# S7CAS-PLEIADES-CARTE-MERE_P06_FPGA4.net
KiCad netlist of a schematic drawn in Altium Designer
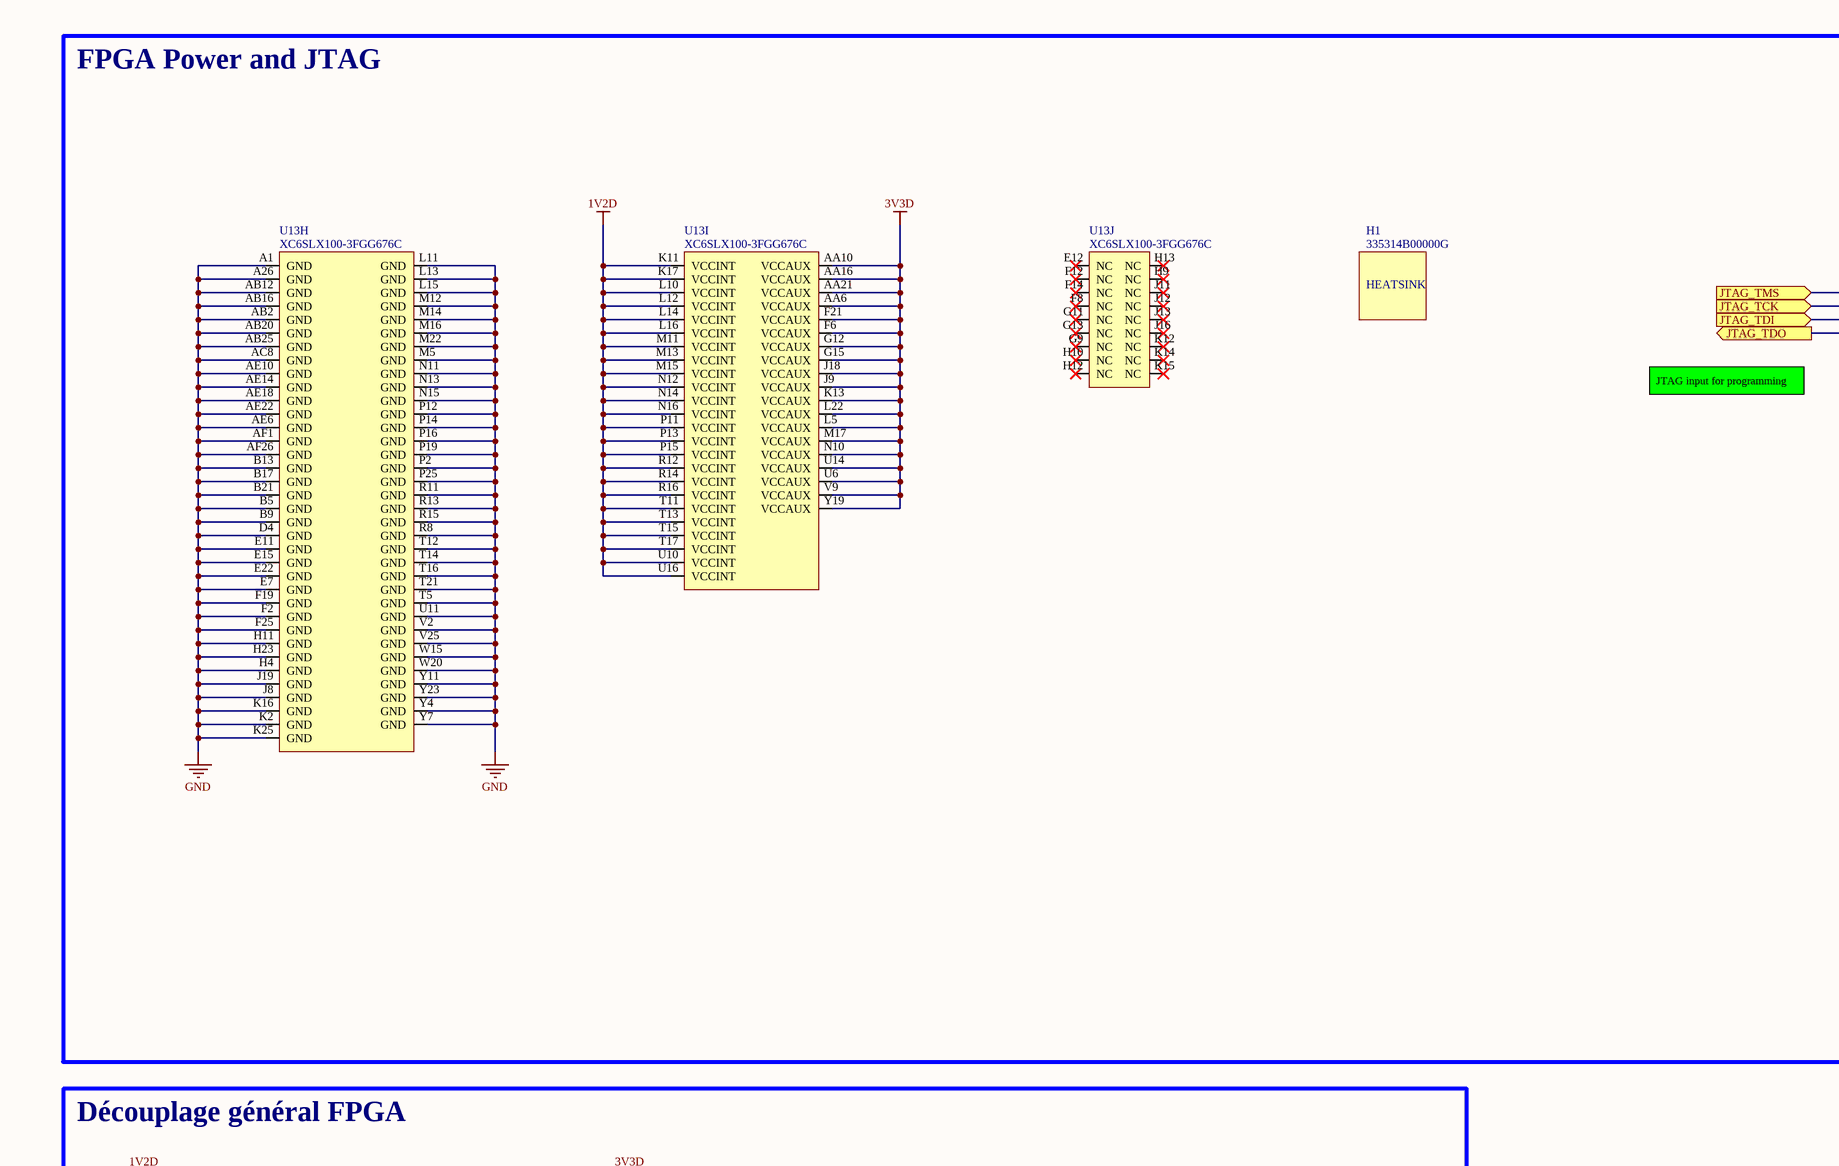
[diagram p0: S7CAS-PLEIADES-CARTE-MERE_P06_FPGA4.SCHDOC, top left]
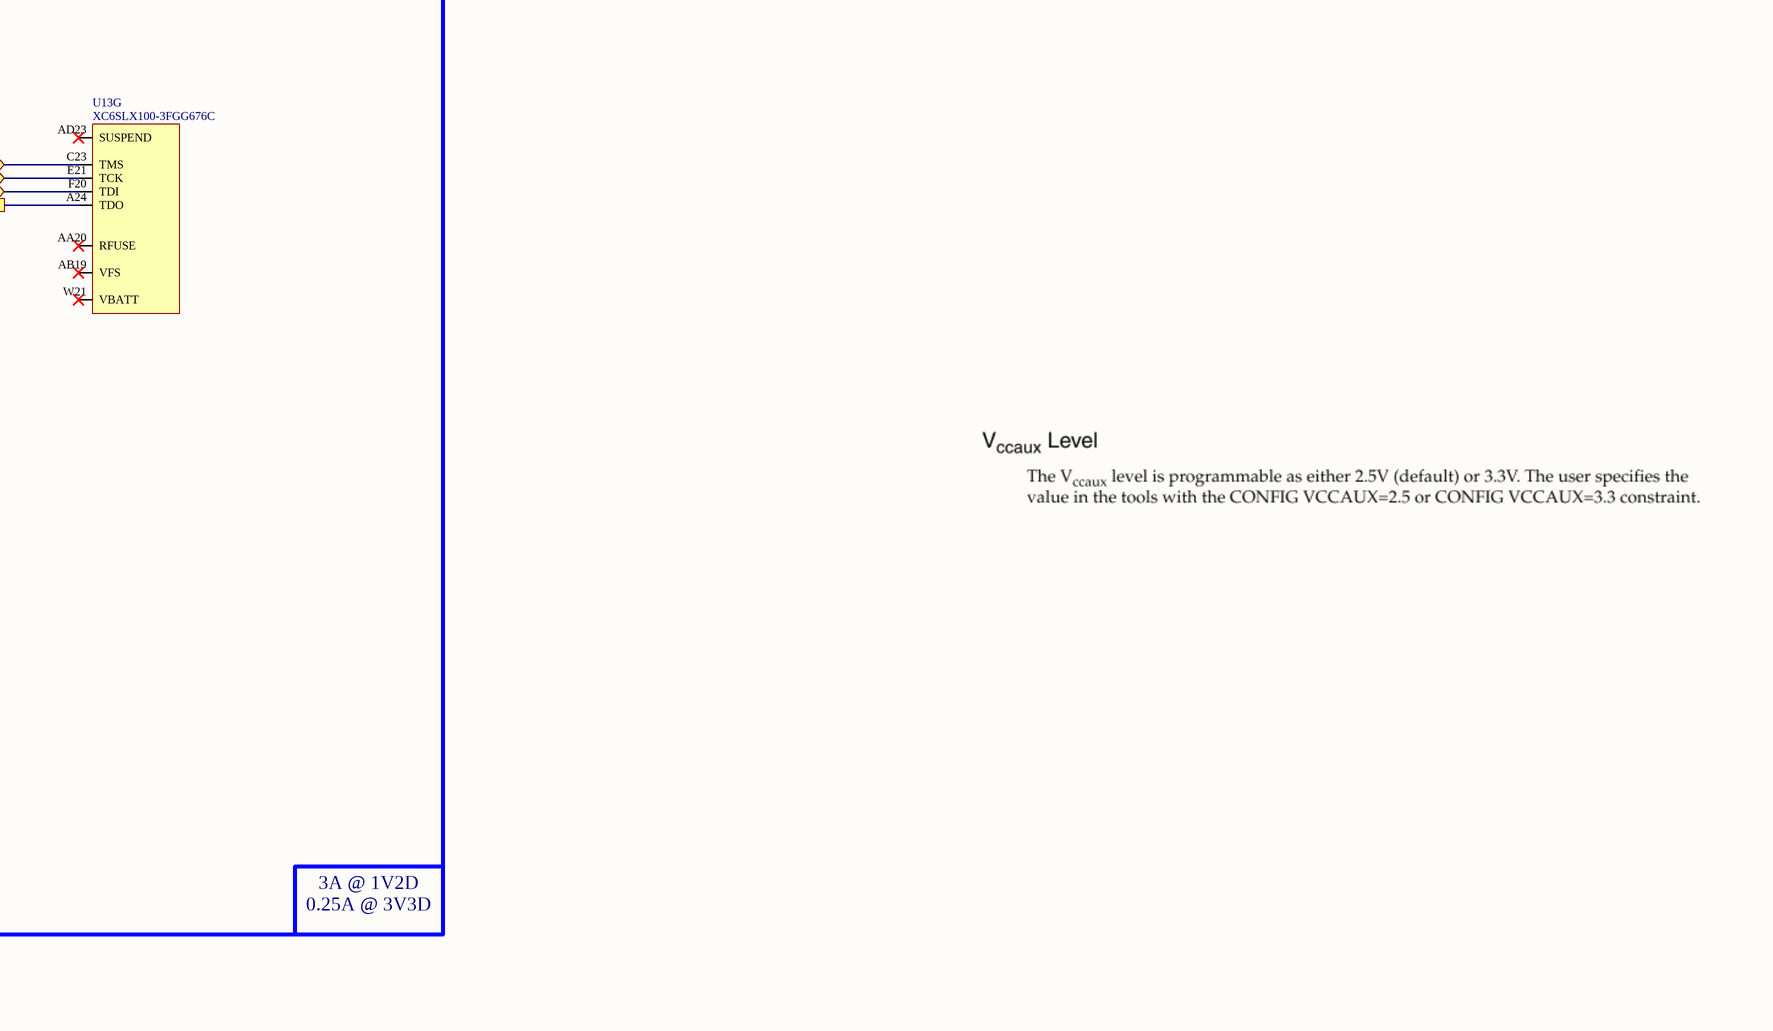
[diagram p1: S7CAS-PLEIADES-CARTE-MERE_P06_FPGA4.SCHDOC, top right]
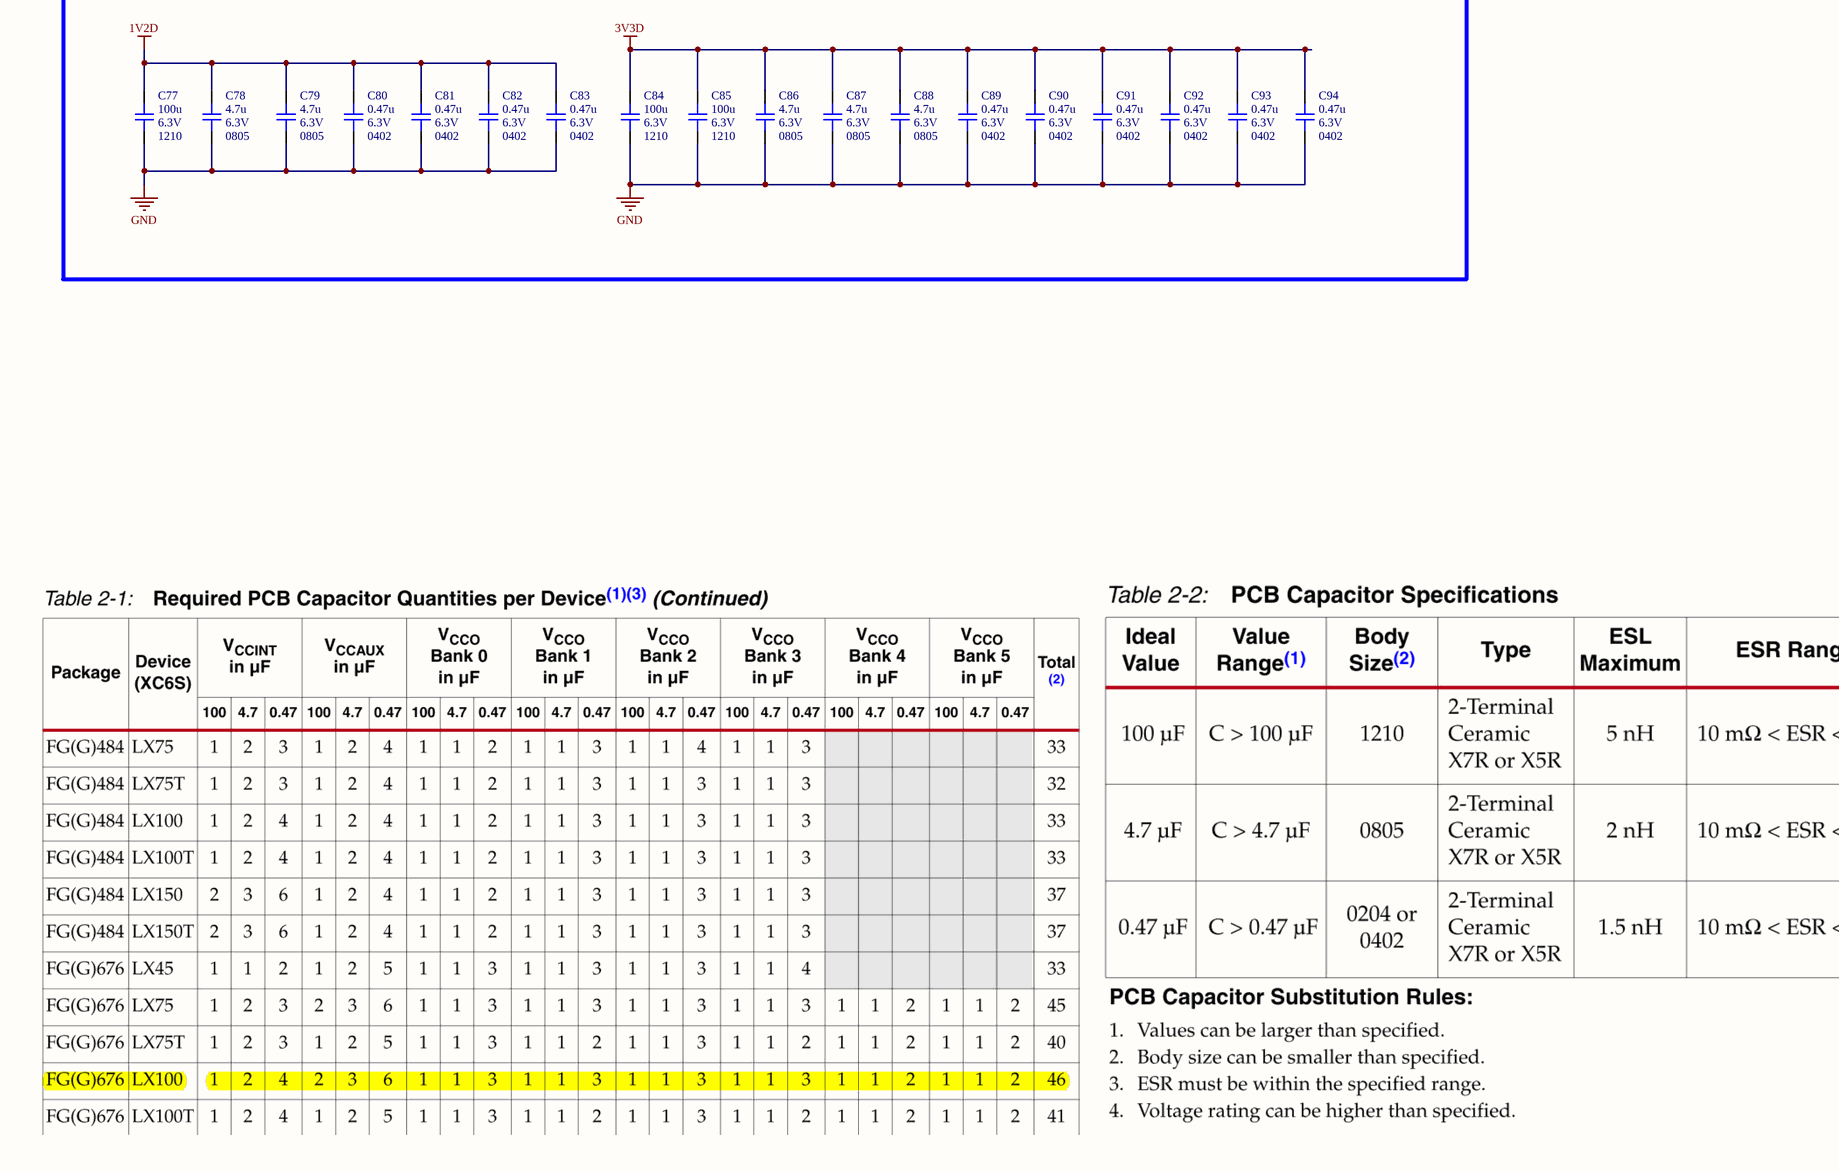
[diagram p2: S7CAS-PLEIADES-CARTE-MERE_P06_FPGA4.SCHDOC, bottom left]
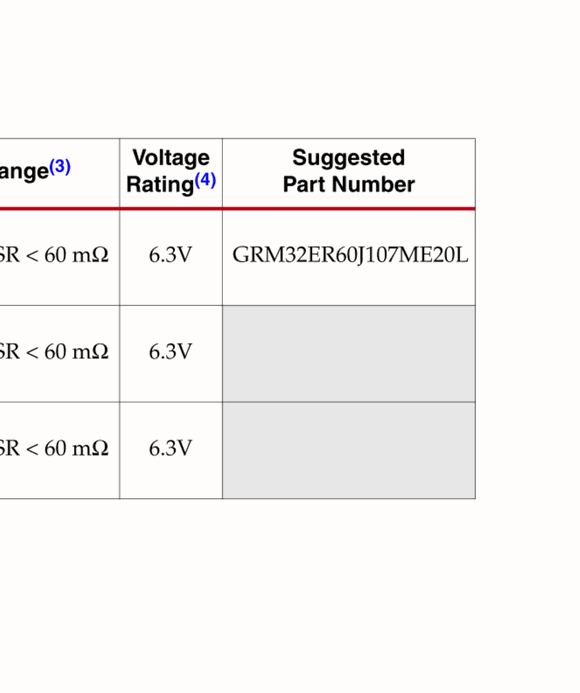
[diagram p3: S7CAS-PLEIADES-CARTE-MERE_P06_FPGA4.SCHDOC, bottom right]

(export (version "E")
  (design (tool "Eeschema 10.0.6"))
  (components
    (comp (ref "C77")
      (value "100u")
      (footprint "CAP_1210")
      (description "CAP - 1210")
      (fields
        (field (name "VOLTAGE") "6.3V")
        (field (name "PACKAGE") "1210")
        (field (name "CREATEDBY") "Jonathan Bouchard")
      )
      (libsource (lib "s7cas_lib2023") (part "CAP - 1210"))
    )
    (comp (ref "C78")
      (value "4.7u")
      (footprint "CAP_0805")
      (description "CAP - 0805")
      (fields
        (field (name "VOLTAGE") "6.3V")
        (field (name "PACKAGE") "0805")
        (field (name "CREATEDBY") "Jonathan Bouchard")
      )
      (libsource (lib "s7cas_lib2023") (part "CAP - 0805"))
    )
    (comp (ref "C79")
      (value "4.7u")
      (footprint "CAP_0805")
      (description "CAP - 0805")
      (fields
        (field (name "VOLTAGE") "6.3V")
        (field (name "PACKAGE") "0805")
        (field (name "CREATEDBY") "Jonathan Bouchard")
      )
      (libsource (lib "s7cas_lib2023") (part "CAP - 0805"))
    )
    (comp (ref "C80")
      (value "0.47u")
      (footprint "CAP_0402")
      (description "CAP - 0402")
      (fields
        (field (name "VOLTAGE") "6.3V")
        (field (name "PACKAGE") "0402")
        (field (name "CREATEDBY") "Jonathan Bouchard")
      )
      (libsource (lib "s7cas_lib2023") (part "CAP - 0402"))
    )
    (comp (ref "C81")
      (value "0.47u")
      (footprint "CAP_0402")
      (description "CAP - 0402")
      (fields
        (field (name "VOLTAGE") "6.3V")
        (field (name "PACKAGE") "0402")
        (field (name "CREATEDBY") "Jonathan Bouchard")
      )
      (libsource (lib "s7cas_lib2023") (part "CAP - 0402"))
    )
    (comp (ref "C82")
      (value "0.47u")
      (footprint "CAP_0402")
      (description "CAP - 0402")
      (fields
        (field (name "VOLTAGE") "6.3V")
        (field (name "PACKAGE") "0402")
        (field (name "CREATEDBY") "Jonathan Bouchard")
      )
      (libsource (lib "s7cas_lib2023") (part "CAP - 0402"))
    )
    (comp (ref "C83")
      (value "0.47u")
      (footprint "CAP_0402")
      (description "CAP - 0402")
      (fields
        (field (name "VOLTAGE") "6.3V")
        (field (name "PACKAGE") "0402")
        (field (name "CREATEDBY") "Jonathan Bouchard")
      )
      (libsource (lib "s7cas_lib2023") (part "CAP - 0402"))
    )
    (comp (ref "C84")
      (value "100u")
      (footprint "CAP_1210")
      (description "CAP - 1210")
      (fields
        (field (name "VOLTAGE") "6.3V")
        (field (name "PACKAGE") "1210")
        (field (name "CREATEDBY") "Jonathan Bouchard")
      )
      (libsource (lib "s7cas_lib2023") (part "CAP - 1210"))
    )
    (comp (ref "C85")
      (value "100u")
      (footprint "CAP_1210")
      (description "CAP - 1210")
      (fields
        (field (name "VOLTAGE") "6.3V")
        (field (name "PACKAGE") "1210")
        (field (name "CREATEDBY") "Jonathan Bouchard")
      )
      (libsource (lib "s7cas_lib2023") (part "CAP - 1210"))
    )
    (comp (ref "C86")
      (value "4.7u")
      (footprint "CAP_0805")
      (description "CAP - 0805")
      (fields
        (field (name "VOLTAGE") "6.3V")
        (field (name "PACKAGE") "0805")
        (field (name "CREATEDBY") "Jonathan Bouchard")
      )
      (libsource (lib "s7cas_lib2023") (part "CAP - 0805"))
    )
    (comp (ref "C87")
      (value "4.7u")
      (footprint "CAP_0805")
      (description "CAP - 0805")
      (fields
        (field (name "VOLTAGE") "6.3V")
        (field (name "PACKAGE") "0805")
        (field (name "CREATEDBY") "Jonathan Bouchard")
      )
      (libsource (lib "s7cas_lib2023") (part "CAP - 0805"))
    )
    (comp (ref "C88")
      (value "4.7u")
      (footprint "CAP_0805")
      (description "CAP - 0805")
      (fields
        (field (name "VOLTAGE") "6.3V")
        (field (name "PACKAGE") "0805")
        (field (name "CREATEDBY") "Jonathan Bouchard")
      )
      (libsource (lib "s7cas_lib2023") (part "CAP - 0805"))
    )
    (comp (ref "C89")
      (value "0.47u")
      (footprint "CAP_0402")
      (description "CAP - 0402")
      (fields
        (field (name "VOLTAGE") "6.3V")
        (field (name "PACKAGE") "0402")
        (field (name "CREATEDBY") "Jonathan Bouchard")
      )
      (libsource (lib "s7cas_lib2023") (part "CAP - 0402"))
    )
    (comp (ref "C90")
      (value "0.47u")
      (footprint "CAP_0402")
      (description "CAP - 0402")
      (fields
        (field (name "VOLTAGE") "6.3V")
        (field (name "PACKAGE") "0402")
        (field (name "CREATEDBY") "Jonathan Bouchard")
      )
      (libsource (lib "s7cas_lib2023") (part "CAP - 0402"))
    )
    (comp (ref "C91")
      (value "0.47u")
      (footprint "CAP_0402")
      (description "CAP - 0402")
      (fields
        (field (name "VOLTAGE") "6.3V")
        (field (name "PACKAGE") "0402")
        (field (name "CREATEDBY") "Jonathan Bouchard")
      )
      (libsource (lib "s7cas_lib2023") (part "CAP - 0402"))
    )
    (comp (ref "C92")
      (value "0.47u")
      (footprint "CAP_0402")
      (description "CAP - 0402")
      (fields
        (field (name "VOLTAGE") "6.3V")
        (field (name "PACKAGE") "0402")
        (field (name "CREATEDBY") "Jonathan Bouchard")
      )
      (libsource (lib "s7cas_lib2023") (part "CAP - 0402"))
    )
    (comp (ref "C93")
      (value "0.47u")
      (footprint "CAP_0402")
      (description "CAP - 0402")
      (fields
        (field (name "VOLTAGE") "6.3V")
        (field (name "PACKAGE") "0402")
        (field (name "CREATEDBY") "Jonathan Bouchard")
      )
      (libsource (lib "s7cas_lib2023") (part "CAP - 0402"))
    )
    (comp (ref "C94")
      (value "0.47u")
      (footprint "CAP_0402")
      (description "CAP - 0402")
      (fields
        (field (name "VOLTAGE") "6.3V")
        (field (name "PACKAGE") "0402")
        (field (name "CREATEDBY") "Jonathan Bouchard")
      )
      (libsource (lib "s7cas_lib2023") (part "CAP - 0402"))
    )
    (comp (ref "H1")
      (value "335314B00000G")
      (description "HSK - Heat sink 335314B00000G 27x27mm")
      (libsource (lib "BGAH270-175E") (part "HSK_335314B00000G"))
    )
    (comp (ref "U13")
      (value "XC6SLX100-3FGG676C")
      (footprint "FPGA_XILINX_FGG676")
      (description "FPGA - XILINX SPARTAN 6 480 I/O - BGA-676")
      (fields
        (field (name "VOLTAGE") "1.14 V ~ 1.26 V")
        (field (name "MFG") "Xilinx")
        (field (name "CREATEDBY") "Jonathan Bouchard")
      )
      (libsource (lib "s7cas_lib2023") (part "FPGA_XC6SLX100-3FGG676C"))
    )
  )
  (nets
    (net (code "1") (name "/JTAG_TCK") (class "Default")
      (node (ref "U13") (pin "E21") (pinfunction "TCK_E21") (pintype "passive"))
    )
    (net (code "2") (name "/JTAG_TDI") (class "Default")
      (node (ref "U13") (pin "F20") (pinfunction "TDI_F20") (pintype "passive"))
    )
    (net (code "3") (name "/JTAG_TDO") (class "Default")
      (node (ref "U13") (pin "A24") (pinfunction "TDO_A24") (pintype "passive"))
    )
    (net (code "4") (name "/JTAG_TMS") (class "Default")
      (node (ref "U13") (pin "C23") (pinfunction "TMS_C23") (pintype "passive"))
    )
    (net (code "5") (name "1V2D") (class "Default")
      (node (ref "C77") (pin "2") (pinfunction "2_2") (pintype "passive"))
      (node (ref "C78") (pin "2") (pinfunction "2_2") (pintype "passive"))
      (node (ref "C79") (pin "2") (pinfunction "2_2") (pintype "passive"))
      (node (ref "C80") (pin "2") (pinfunction "2_2") (pintype "passive"))
      (node (ref "C81") (pin "2") (pinfunction "2_2") (pintype "passive"))
      (node (ref "C82") (pin "2") (pinfunction "2_2") (pintype "passive"))
      (node (ref "C83") (pin "2") (pinfunction "2_2") (pintype "passive"))
      (node (ref "U13") (pin "K11") (pinfunction "VCCINT_K11") (pintype "passive"))
      (node (ref "U13") (pin "K17") (pinfunction "VCCINT_K17") (pintype "passive"))
      (node (ref "U13") (pin "L10") (pinfunction "VCCINT_L10") (pintype "passive"))
      (node (ref "U13") (pin "L12") (pinfunction "VCCINT_L12") (pintype "passive"))
      (node (ref "U13") (pin "L14") (pinfunction "VCCINT_L14") (pintype "passive"))
      (node (ref "U13") (pin "L16") (pinfunction "VCCINT_L16") (pintype "passive"))
      (node (ref "U13") (pin "M11") (pinfunction "VCCINT_M11") (pintype "passive"))
      (node (ref "U13") (pin "M13") (pinfunction "VCCINT_M13") (pintype "passive"))
      (node (ref "U13") (pin "M15") (pinfunction "VCCINT_M15") (pintype "passive"))
      (node (ref "U13") (pin "N12") (pinfunction "VCCINT_N12") (pintype "passive"))
      (node (ref "U13") (pin "N14") (pinfunction "VCCINT_N14") (pintype "passive"))
      (node (ref "U13") (pin "N16") (pinfunction "VCCINT_N16") (pintype "passive"))
      (node (ref "U13") (pin "P11") (pinfunction "VCCINT_P11") (pintype "passive"))
      (node (ref "U13") (pin "P13") (pinfunction "VCCINT_P13") (pintype "passive"))
      (node (ref "U13") (pin "P15") (pinfunction "VCCINT_P15") (pintype "passive"))
      (node (ref "U13") (pin "R12") (pinfunction "VCCINT_R12") (pintype "passive"))
      (node (ref "U13") (pin "R14") (pinfunction "VCCINT_R14") (pintype "passive"))
      (node (ref "U13") (pin "R16") (pinfunction "VCCINT_R16") (pintype "passive"))
      (node (ref "U13") (pin "T11") (pinfunction "VCCINT_T11") (pintype "passive"))
      (node (ref "U13") (pin "T13") (pinfunction "VCCINT_T13") (pintype "passive"))
      (node (ref "U13") (pin "T15") (pinfunction "VCCINT_T15") (pintype "passive"))
      (node (ref "U13") (pin "T17") (pinfunction "VCCINT_T17") (pintype "passive"))
      (node (ref "U13") (pin "U10") (pinfunction "VCCINT_U10") (pintype "passive"))
      (node (ref "U13") (pin "U16") (pinfunction "VCCINT_U16") (pintype "passive"))
    )
    (net (code "6") (name "3V3D") (class "Default")
      (node (ref "C84") (pin "2") (pinfunction "2_2") (pintype "passive"))
      (node (ref "C85") (pin "2") (pinfunction "2_2") (pintype "passive"))
      (node (ref "C86") (pin "2") (pinfunction "2_2") (pintype "passive"))
      (node (ref "C87") (pin "2") (pinfunction "2_2") (pintype "passive"))
      (node (ref "C88") (pin "2") (pinfunction "2_2") (pintype "passive"))
      (node (ref "C89") (pin "2") (pinfunction "2_2") (pintype "passive"))
      (node (ref "C90") (pin "2") (pinfunction "2_2") (pintype "passive"))
      (node (ref "C91") (pin "2") (pinfunction "2_2") (pintype "passive"))
      (node (ref "C92") (pin "2") (pinfunction "2_2") (pintype "passive"))
      (node (ref "C93") (pin "2") (pinfunction "2_2") (pintype "passive"))
      (node (ref "C94") (pin "2") (pinfunction "2_2") (pintype "passive"))
      (node (ref "U13") (pin "AA10") (pinfunction "VCCAUX_AA10") (pintype "passive"))
      (node (ref "U13") (pin "AA16") (pinfunction "VCCAUX_AA16") (pintype "passive"))
      (node (ref "U13") (pin "AA21") (pinfunction "VCCAUX_AA21") (pintype "passive"))
      (node (ref "U13") (pin "AA6") (pinfunction "VCCAUX_AA6") (pintype "passive"))
      (node (ref "U13") (pin "F21") (pinfunction "VCCAUX_F21") (pintype "passive"))
      (node (ref "U13") (pin "F6") (pinfunction "VCCAUX_F6") (pintype "passive"))
      (node (ref "U13") (pin "G12") (pinfunction "VCCAUX_G12") (pintype "passive"))
      (node (ref "U13") (pin "G15") (pinfunction "VCCAUX_G15") (pintype "passive"))
      (node (ref "U13") (pin "J18") (pinfunction "VCCAUX_J18") (pintype "passive"))
      (node (ref "U13") (pin "J9") (pinfunction "VCCAUX_J9") (pintype "passive"))
      (node (ref "U13") (pin "K13") (pinfunction "VCCAUX_K13") (pintype "passive"))
      (node (ref "U13") (pin "L22") (pinfunction "VCCAUX_L22") (pintype "passive"))
      (node (ref "U13") (pin "L5") (pinfunction "VCCAUX_L5") (pintype "passive"))
      (node (ref "U13") (pin "M17") (pinfunction "VCCAUX_M17") (pintype "passive"))
      (node (ref "U13") (pin "N10") (pinfunction "VCCAUX_N10") (pintype "passive"))
      (node (ref "U13") (pin "U14") (pinfunction "VCCAUX_U14") (pintype "passive"))
      (node (ref "U13") (pin "U6") (pinfunction "VCCAUX_U6") (pintype "passive"))
      (node (ref "U13") (pin "V9") (pinfunction "VCCAUX_V9") (pintype "passive"))
      (node (ref "U13") (pin "Y19") (pinfunction "VCCAUX_Y19") (pintype "passive"))
    )
    (net (code "7") (name "GND") (class "Default")
      (node (ref "C77") (pin "1") (pinfunction "1_1") (pintype "passive"))
      (node (ref "C78") (pin "1") (pinfunction "1_1") (pintype "passive"))
      (node (ref "C79") (pin "1") (pinfunction "1_1") (pintype "passive"))
      (node (ref "C80") (pin "1") (pinfunction "1_1") (pintype "passive"))
      (node (ref "C81") (pin "1") (pinfunction "1_1") (pintype "passive"))
      (node (ref "C82") (pin "1") (pinfunction "1_1") (pintype "passive"))
      (node (ref "C83") (pin "1") (pinfunction "1_1") (pintype "passive"))
      (node (ref "C84") (pin "1") (pinfunction "1_1") (pintype "passive"))
      (node (ref "C85") (pin "1") (pinfunction "1_1") (pintype "passive"))
      (node (ref "C86") (pin "1") (pinfunction "1_1") (pintype "passive"))
      (node (ref "C87") (pin "1") (pinfunction "1_1") (pintype "passive"))
      (node (ref "C88") (pin "1") (pinfunction "1_1") (pintype "passive"))
      (node (ref "C89") (pin "1") (pinfunction "1_1") (pintype "passive"))
      (node (ref "C90") (pin "1") (pinfunction "1_1") (pintype "passive"))
      (node (ref "C91") (pin "1") (pinfunction "1_1") (pintype "passive"))
      (node (ref "C92") (pin "1") (pinfunction "1_1") (pintype "passive"))
      (node (ref "C93") (pin "1") (pinfunction "1_1") (pintype "passive"))
      (node (ref "C94") (pin "1") (pinfunction "1_1") (pintype "passive"))
      (node (ref "U13") (pin "A1") (pinfunction "GND_A1") (pintype "passive"))
      (node (ref "U13") (pin "A26") (pinfunction "GND_A26") (pintype "passive"))
      (node (ref "U13") (pin "AB12") (pinfunction "GND_AB12") (pintype "passive"))
      (node (ref "U13") (pin "AB16") (pinfunction "GND_AB16") (pintype "passive"))
      (node (ref "U13") (pin "AB2") (pinfunction "GND_AB2") (pintype "passive"))
      (node (ref "U13") (pin "AB20") (pinfunction "GND_AB20") (pintype "passive"))
      (node (ref "U13") (pin "AB25") (pinfunction "GND_AB25") (pintype "passive"))
      (node (ref "U13") (pin "AC8") (pinfunction "GND_AC8") (pintype "passive"))
      (node (ref "U13") (pin "AE10") (pinfunction "GND_AE10") (pintype "passive"))
      (node (ref "U13") (pin "AE14") (pinfunction "GND_AE14") (pintype "passive"))
      (node (ref "U13") (pin "AE18") (pinfunction "GND_AE18") (pintype "passive"))
      (node (ref "U13") (pin "AE22") (pinfunction "GND_AE22") (pintype "passive"))
      (node (ref "U13") (pin "AE6") (pinfunction "GND_AE6") (pintype "passive"))
      (node (ref "U13") (pin "AF1") (pinfunction "GND_AF1") (pintype "passive"))
      (node (ref "U13") (pin "AF26") (pinfunction "GND_AF26") (pintype "passive"))
      (node (ref "U13") (pin "B13") (pinfunction "GND_B13") (pintype "passive"))
      (node (ref "U13") (pin "B17") (pinfunction "GND_B17") (pintype "passive"))
      (node (ref "U13") (pin "B21") (pinfunction "GND_B21") (pintype "passive"))
      (node (ref "U13") (pin "B5") (pinfunction "GND_B5") (pintype "passive"))
      (node (ref "U13") (pin "B9") (pinfunction "GND_B9") (pintype "passive"))
      (node (ref "U13") (pin "D4") (pinfunction "GND_D4") (pintype "passive"))
      (node (ref "U13") (pin "E11") (pinfunction "GND_E11") (pintype "passive"))
      (node (ref "U13") (pin "E15") (pinfunction "GND_E15") (pintype "passive"))
      (node (ref "U13") (pin "E22") (pinfunction "GND_E22") (pintype "passive"))
      (node (ref "U13") (pin "E7") (pinfunction "GND_E7") (pintype "passive"))
      (node (ref "U13") (pin "F19") (pinfunction "GND_F19") (pintype "passive"))
      (node (ref "U13") (pin "F2") (pinfunction "GND_F2") (pintype "passive"))
      (node (ref "U13") (pin "F25") (pinfunction "GND_F25") (pintype "passive"))
      (node (ref "U13") (pin "H11") (pinfunction "GND_H11") (pintype "passive"))
      (node (ref "U13") (pin "H23") (pinfunction "GND_H23") (pintype "passive"))
      (node (ref "U13") (pin "H4") (pinfunction "GND_H4") (pintype "passive"))
      (node (ref "U13") (pin "J19") (pinfunction "GND_J19") (pintype "passive"))
      (node (ref "U13") (pin "J8") (pinfunction "GND_J8") (pintype "passive"))
      (node (ref "U13") (pin "K16") (pinfunction "GND_K16") (pintype "passive"))
      (node (ref "U13") (pin "K2") (pinfunction "GND_K2") (pintype "passive"))
      (node (ref "U13") (pin "K25") (pinfunction "GND_K25") (pintype "passive"))
      (node (ref "U13") (pin "L11") (pinfunction "GND_L11") (pintype "passive"))
      (node (ref "U13") (pin "L13") (pinfunction "GND_L13") (pintype "passive"))
      (node (ref "U13") (pin "L15") (pinfunction "GND_L15") (pintype "passive"))
      (node (ref "U13") (pin "M12") (pinfunction "GND_M12") (pintype "passive"))
      (node (ref "U13") (pin "M14") (pinfunction "GND_M14") (pintype "passive"))
      (node (ref "U13") (pin "M16") (pinfunction "GND_M16") (pintype "passive"))
      (node (ref "U13") (pin "M22") (pinfunction "GND_M22") (pintype "passive"))
      (node (ref "U13") (pin "M5") (pinfunction "GND_M5") (pintype "passive"))
      (node (ref "U13") (pin "N11") (pinfunction "GND_N11") (pintype "passive"))
      (node (ref "U13") (pin "N13") (pinfunction "GND_N13") (pintype "passive"))
      (node (ref "U13") (pin "N15") (pinfunction "GND_N15") (pintype "passive"))
      (node (ref "U13") (pin "P12") (pinfunction "GND_P12") (pintype "passive"))
      (node (ref "U13") (pin "P14") (pinfunction "GND_P14") (pintype "passive"))
      (node (ref "U13") (pin "P16") (pinfunction "GND_P16") (pintype "passive"))
      (node (ref "U13") (pin "P19") (pinfunction "GND_P19") (pintype "passive"))
      (node (ref "U13") (pin "P2") (pinfunction "GND_P2") (pintype "passive"))
      (node (ref "U13") (pin "P25") (pinfunction "GND_P25") (pintype "passive"))
      (node (ref "U13") (pin "R11") (pinfunction "GND_R11") (pintype "passive"))
      (node (ref "U13") (pin "R13") (pinfunction "GND_R13") (pintype "passive"))
      (node (ref "U13") (pin "R15") (pinfunction "GND_R15") (pintype "passive"))
      (node (ref "U13") (pin "R8") (pinfunction "GND_R8") (pintype "passive"))
      (node (ref "U13") (pin "T12") (pinfunction "GND_T12") (pintype "passive"))
      (node (ref "U13") (pin "T14") (pinfunction "GND_T14") (pintype "passive"))
      (node (ref "U13") (pin "T16") (pinfunction "GND_T16") (pintype "passive"))
      (node (ref "U13") (pin "T21") (pinfunction "GND_T21") (pintype "passive"))
      (node (ref "U13") (pin "T5") (pinfunction "GND_T5") (pintype "passive"))
      (node (ref "U13") (pin "U11") (pinfunction "GND_U11") (pintype "passive"))
      (node (ref "U13") (pin "V2") (pinfunction "GND_V2") (pintype "passive"))
      (node (ref "U13") (pin "V25") (pinfunction "GND_V25") (pintype "passive"))
      (node (ref "U13") (pin "W15") (pinfunction "GND_W15") (pintype "passive"))
      (node (ref "U13") (pin "W20") (pinfunction "GND_W20") (pintype "passive"))
      (node (ref "U13") (pin "Y11") (pinfunction "GND_Y11") (pintype "passive"))
      (node (ref "U13") (pin "Y23") (pinfunction "GND_Y23") (pintype "passive"))
      (node (ref "U13") (pin "Y4") (pinfunction "GND_Y4") (pintype "passive"))
      (node (ref "U13") (pin "Y7") (pinfunction "GND_Y7") (pintype "passive"))
    )
    (net (code "8") (name "unconnected-(U13G-RFUSE-PadAA20)") (class "Default")
      (node (ref "U13") (pin "AA20") (pinfunction "RFUSE_AA20") (pintype "passive+no_connect"))
    )
    (net (code "9") (name "unconnected-(U13G-SUSPEND-PadAD23)") (class "Default")
      (node (ref "U13") (pin "AD23") (pinfunction "SUSPEND_AD23") (pintype "passive+no_connect"))
    )
    (net (code "10") (name "unconnected-(U13G-VBATT-PadW21)") (class "Default")
      (node (ref "U13") (pin "W21") (pinfunction "VBATT_W21") (pintype "passive+no_connect"))
    )
    (net (code "11") (name "unconnected-(U13G-VFS-PadAB19)") (class "Default")
      (node (ref "U13") (pin "AB19") (pinfunction "VFS_AB19") (pintype "passive+no_connect"))
    )
    (net (code "12") (name "unconnected-(U13J-NC-PadE12)") (class "Default")
      (node (ref "U13") (pin "E12") (pinfunction "NC_E12") (pintype "passive+no_connect"))
    )
    (net (code "13") (name "unconnected-(U13J-NC-PadF8)") (class "Default")
      (node (ref "U13") (pin "F8") (pinfunction "NC_F8") (pintype "passive+no_connect"))
    )
    (net (code "14") (name "unconnected-(U13J-NC-PadF12)") (class "Default")
      (node (ref "U13") (pin "F12") (pinfunction "NC_F12") (pintype "passive+no_connect"))
    )
    (net (code "15") (name "unconnected-(U13J-NC-PadF14)") (class "Default")
      (node (ref "U13") (pin "F14") (pinfunction "NC_F14") (pintype "passive+no_connect"))
    )
    (net (code "16") (name "unconnected-(U13J-NC-PadG9)") (class "Default")
      (node (ref "U13") (pin "G9") (pinfunction "NC_G9") (pintype "passive+no_connect"))
    )
    (net (code "17") (name "unconnected-(U13J-NC-PadG11)") (class "Default")
      (node (ref "U13") (pin "G11") (pinfunction "NC_G11") (pintype "passive+no_connect"))
    )
    (net (code "18") (name "unconnected-(U13J-NC-PadG13)") (class "Default")
      (node (ref "U13") (pin "G13") (pinfunction "NC_G13") (pintype "passive+no_connect"))
    )
    (net (code "19") (name "unconnected-(U13J-NC-PadH9)") (class "Default")
      (node (ref "U13") (pin "H9") (pinfunction "NC_H9") (pintype "passive+no_connect"))
    )
    (net (code "20") (name "unconnected-(U13J-NC-PadH10)") (class "Default")
      (node (ref "U13") (pin "H10") (pinfunction "NC_H10") (pintype "passive+no_connect"))
    )
    (net (code "21") (name "unconnected-(U13J-NC-PadH12)") (class "Default")
      (node (ref "U13") (pin "H12") (pinfunction "NC_H12") (pintype "passive+no_connect"))
    )
    (net (code "22") (name "unconnected-(U13J-NC-PadH13)") (class "Default")
      (node (ref "U13") (pin "H13") (pinfunction "NC_H13") (pintype "passive+no_connect"))
    )
    (net (code "23") (name "unconnected-(U13J-NC-PadJ11)") (class "Default")
      (node (ref "U13") (pin "J11") (pinfunction "NC_J11") (pintype "passive+no_connect"))
    )
    (net (code "24") (name "unconnected-(U13J-NC-PadJ12)") (class "Default")
      (node (ref "U13") (pin "J12") (pinfunction "NC_J12") (pintype "passive+no_connect"))
    )
    (net (code "25") (name "unconnected-(U13J-NC-PadJ13)") (class "Default")
      (node (ref "U13") (pin "J13") (pinfunction "NC_J13") (pintype "passive+no_connect"))
    )
    (net (code "26") (name "unconnected-(U13J-NC-PadJ16)") (class "Default")
      (node (ref "U13") (pin "J16") (pinfunction "NC_J16") (pintype "passive+no_connect"))
    )
    (net (code "27") (name "unconnected-(U13J-NC-PadK12)") (class "Default")
      (node (ref "U13") (pin "K12") (pinfunction "NC_K12") (pintype "passive+no_connect"))
    )
    (net (code "28") (name "unconnected-(U13J-NC-PadK14)") (class "Default")
      (node (ref "U13") (pin "K14") (pinfunction "NC_K14") (pintype "passive+no_connect"))
    )
    (net (code "29") (name "unconnected-(U13J-NC-PadK15)") (class "Default")
      (node (ref "U13") (pin "K15") (pinfunction "NC_K15") (pintype "passive+no_connect"))
    )
  )
)
